# Pyr0-Piezo_Direct_Extruder_Board2_3_1.net
KiCad netlist of a schematic drawn in EAGLE
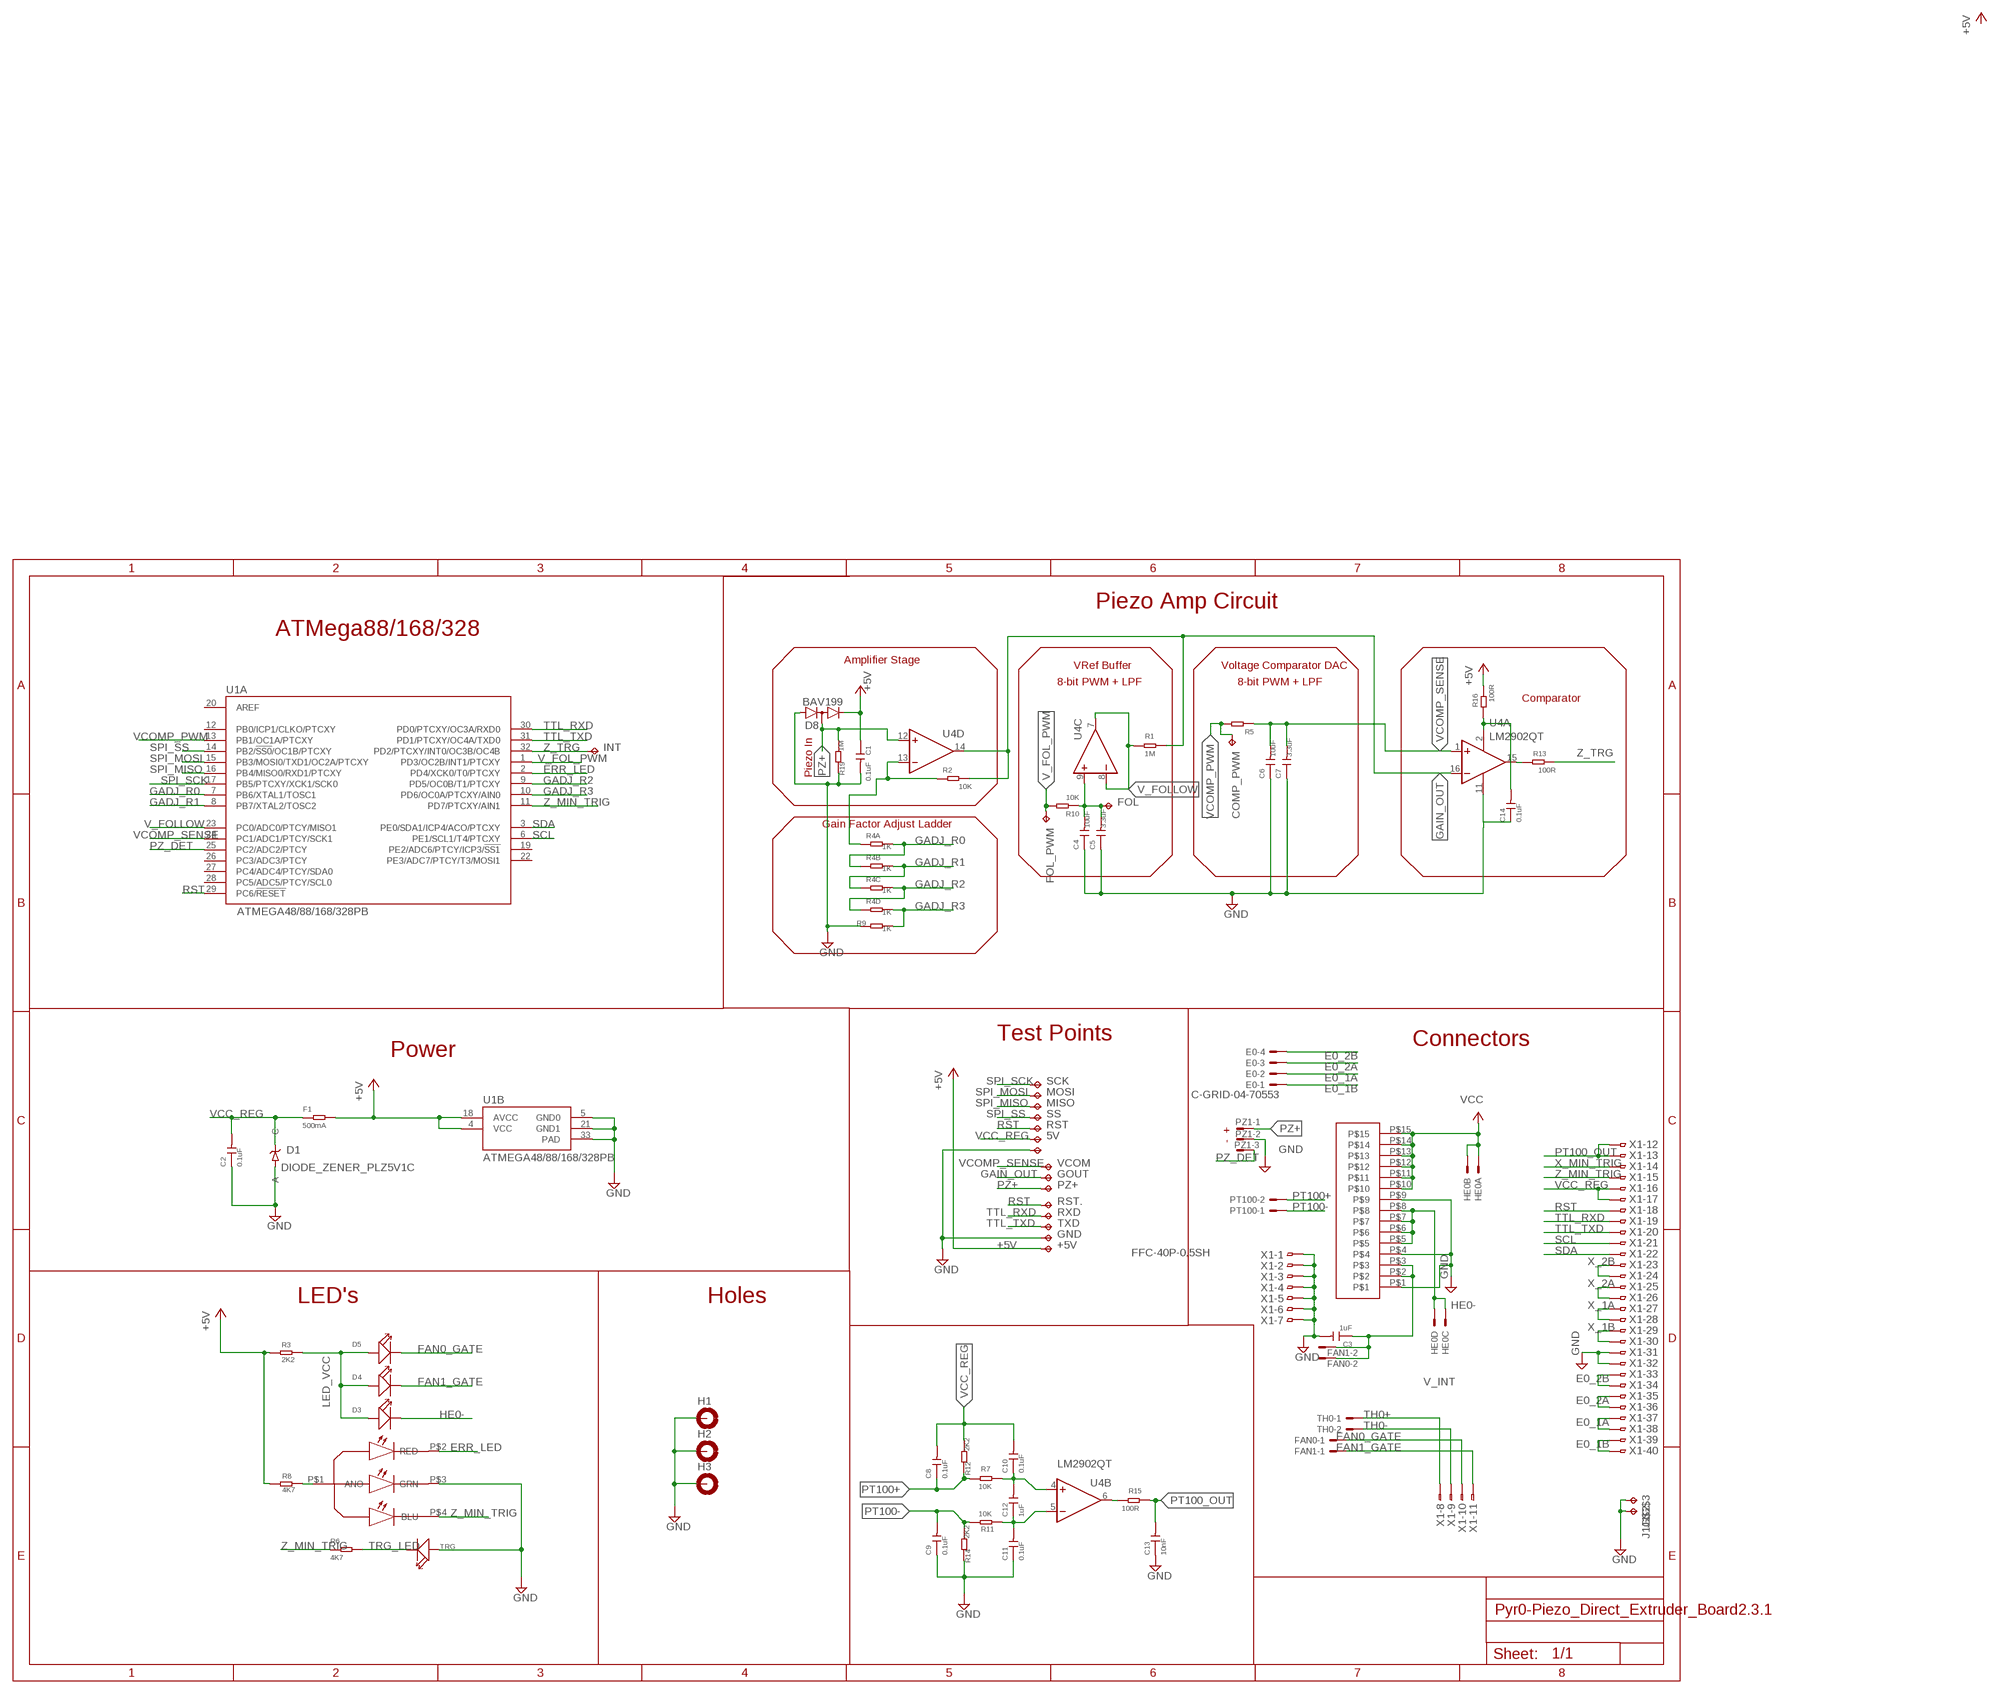
[diagram p0: schematic, sheet 1]

(export (version "E")
  (design (tool "Eeschema 10.0.6"))
  (components
    (comp (ref "+5V")
      (value "TPTP13SQ")
      (footprint "eagle-import:TP13SQ")
      (libsource (lib "eagle-import") (part "testpad_385_TPTP13SQ"))
    )
    (comp (ref "5V")
      (value "TPTP13SQ")
      (footprint "eagle-import:TP13SQ")
      (libsource (lib "eagle-import") (part "TPTP13SQ"))
    )
    (comp (ref "C1")
      (value "0.1uF")
      (footprint "eagle-import:CAPC2012X130")
      (libsource (lib "eagle-import") (part "SEEED-CAPACITOR_CERAMIC-10UF-25V-10%-X5R(0805)CAP_0805-3D"))
    )
    (comp (ref "C2")
      (value "0.1uF")
      (footprint "eagle-import:CAPC1005X50")
      (libsource (lib "eagle-import") (part "CERAMIC-1NF-50V-10%-X7R(0402)CAP_0402"))
    )
    (comp (ref "C3")
      (value "1uF")
      (footprint "eagle-import:CAPC1609X80")
      (libsource (lib "eagle-import") (part "SEEED-CAPACITOR_CERAMIC-10UF-25V-10%-X5R(0805)CAP_0603_GEN"))
    )
    (comp (ref "C4")
      (value "10uF")
      (footprint "eagle-import:CAPC1005X50")
      (libsource (lib "eagle-import") (part "CERAMIC-1NF-50V-10%-X7R(0402)CAP_0402"))
    )
    (comp (ref "C5")
      (value "3.3uF")
      (footprint "eagle-import:CAPC1609X80")
      (libsource (lib "eagle-import") (part "SEEED-CAPACITOR_CERAMIC-10UF-25V-10%-X5R(0805)CAP_0603_GEN"))
    )
    (comp (ref "C6")
      (value "10uF")
      (footprint "eagle-import:CAPC1005X50")
      (libsource (lib "eagle-import") (part "CERAMIC-1NF-50V-10%-X7R(0402)CAP_0402"))
    )
    (comp (ref "C7")
      (value "3.3uF")
      (footprint "eagle-import:CAPC1609X80")
      (libsource (lib "eagle-import") (part "SEEED-CAPACITOR_CERAMIC-10UF-25V-10%-X5R(0805)CAP_0603_GEN"))
    )
    (comp (ref "C8")
      (value "0.1uF")
      (footprint "eagle-import:CAPC1005X50")
      (libsource (lib "eagle-import") (part "CERAMIC-1NF-50V-10%-X7R(0402)CAP_0402"))
    )
    (comp (ref "C9")
      (value "0.1uF")
      (footprint "eagle-import:CAPC1005X50")
      (libsource (lib "eagle-import") (part "CERAMIC-1NF-50V-10%-X7R(0402)CAP_0402"))
    )
    (comp (ref "C10")
      (value "0.1uF")
      (footprint "eagle-import:CAPC1005X50")
      (libsource (lib "eagle-import") (part "CERAMIC-1NF-50V-10%-X7R(0402)CAP_0402"))
    )
    (comp (ref "C11")
      (value "0.1uF")
      (footprint "eagle-import:CAPC1005X50")
      (libsource (lib "eagle-import") (part "CERAMIC-1NF-50V-10%-X7R(0402)CAP_0402"))
    )
    (comp (ref "C12")
      (value "1uF")
      (footprint "eagle-import:CAPC1005X50")
      (libsource (lib "eagle-import") (part "CERAMIC-1NF-50V-10%-X7R(0402)CAP_0402"))
    )
    (comp (ref "C13")
      (value "10nF")
      (footprint "eagle-import:CAPC1005X50")
      (libsource (lib "eagle-import") (part "CERAMIC-1NF-50V-10%-X7R(0402)CAP_0402"))
    )
    (comp (ref "C14")
      (value "0.1uF")
      (footprint "eagle-import:CAPC1005X50")
      (libsource (lib "eagle-import") (part "CERAMIC-1NF-50V-10%-X7R(0402)CAP_0402"))
    )
    (comp (ref "COMP_PWM")
      (value "TPTP09R")
      (footprint "eagle-import:TP09R")
      (libsource (lib "eagle-import") (part "TPTP09R"))
    )
    (comp (ref "D1")
      (value "DIODE_ZENER_PLZ5V1C")
      (footprint "eagle-import:DO-219AC")
      (libsource (lib "eagle-import") (part "DIODE_ZENER_PLZ5V1C"))
    )
    (comp (ref "D2")
      (value "LED-RGB-COM_ANO4PLCC")
      (footprint "eagle-import:4PLCC")
      (libsource (lib "eagle-import") (part "LED-RGB-COM_ANO4PLCC"))
    )
    (comp (ref "D3")
      (value "SEEED-LED_SMD-LED-CLEAR-BLUE(0603)LED_0603")
      (footprint "eagle-import:SEEED-LED_LED-0603")
      (libsource (lib "eagle-import") (part "SEEED-LED_SMD-LED-CLEAR-BLUE(0603)LED_0603"))
    )
    (comp (ref "D4")
      (value "SEEED-LED_SMD-LED-CLEAR-BLUE(0603)LED_0603")
      (footprint "eagle-import:SEEED-LED_LED-0603")
      (libsource (lib "eagle-import") (part "SEEED-LED_SMD-LED-CLEAR-BLUE(0603)LED_0603"))
    )
    (comp (ref "D5")
      (value "SEEED-LED_SMD-LED-CLEAR-BLUE(0603)LED_0603")
      (footprint "eagle-import:SEEED-LED_LED-0603")
      (libsource (lib "eagle-import") (part "SEEED-LED_SMD-LED-CLEAR-BLUE(0603)LED_0603"))
    )
    (comp (ref "D8")
      (value "BAV199")
      (footprint "eagle-import:SOT23")
      (libsource (lib "eagle-import") (part "BAV199"))
    )
    (comp (ref "E0")
      (value "C-GRID-04-70553")
      (footprint "eagle-import:70553-04")
      (fields (field (name "MF") "MOLEX"))
      (libsource (lib "eagle-import") (part "C-GRID-04-70553"))
    )
    (comp (ref "F1")
      (value "500mA")
      (footprint "eagle-import:SEEED-RESISTOR_R0603")
      (libsource (lib "eagle-import") (part "SEEED-RESISTOR_SMD-RES-1.5K-1%-1/10W(0603)DETAILED_MODEL"))
    )
    (comp (ref "FAN0")
      (value "CON-MOLEX-2P-1.27MM048")
      (footprint "eagle-import:53048-02")
      (fields (field (name "MF") "MOLEX") (field (name "MPN") "53048-0210"))
      (libsource (lib "eagle-import") (part "CON-MOLEX-2P-1.27MM048"))
    )
    (comp (ref "FAN1")
      (value "CON-MOLEX-2P-1.27MM048")
      (footprint "eagle-import:53048-02")
      (fields (field (name "MF") "MOLEX") (field (name "MPN") "53048-0210"))
      (libsource (lib "eagle-import") (part "CON-MOLEX-2P-1.27MM048"))
    )
    (comp (ref "FOL")
      (value "TPTP13SQ")
      (footprint "eagle-import:TP13SQ")
      (libsource (lib "eagle-import") (part "TPTP13SQ"))
    )
    (comp (ref "FOL_PWM")
      (value "TPTP09R")
      (footprint "eagle-import:TP09R")
      (libsource (lib "eagle-import") (part "TPTP09R"))
    )
    (comp (ref "GND")
      (value "TPTP13SQ")
      (footprint "eagle-import:TP13SQ")
      (libsource (lib "eagle-import") (part "testpad_385_TPTP13SQ"))
    )
    (comp (ref "GOUT")
      (value "TPTP13SQ")
      (footprint "eagle-import:TP13SQ")
      (libsource (lib "eagle-import") (part "TPTP13SQ"))
    )
    (comp (ref "H1")
      (value "HOLES_MOUNT-PAD-ROUND3.2")
      (footprint "eagle-import:HOLES_3,2-PAD")
      (libsource (lib "eagle-import") (part "HOLES_MOUNT-PAD-ROUND3.2"))
    )
    (comp (ref "H2")
      (value "HOLES_MOUNT-PAD-ROUND3.2")
      (footprint "eagle-import:HOLES_3,2-PAD")
      (libsource (lib "eagle-import") (part "HOLES_MOUNT-PAD-ROUND3.2"))
    )
    (comp (ref "H3")
      (value "HOLES_MOUNT-PAD-ROUND3.2")
      (footprint "eagle-import:HOLES_3,2-PAD")
      (libsource (lib "eagle-import") (part "HOLES_MOUNT-PAD-ROUND3.2"))
    )
    (comp (ref "HE0")
      (value "JST-2.54-2X2JST-DUPONT-2.54-2X2")
      (footprint "eagle-import:HDRRAR4W64P254_2X2_556X736X556B")
      (libsource (lib "eagle-import") (part "JST-2.54-2X2JST-DUPONT-2.54-2X2"))
    )
    (comp (ref "INT")
      (value "TPTP13R")
      (footprint "eagle-import:TP13R")
      (libsource (lib "eagle-import") (part "TPTP13R"))
    )
    (comp (ref "J1")
      (value "FFC-15P-1MM")
      (footprint "eagle-import:FFC-15P-1MM")
      (libsource (lib "eagle-import") (part "FFC-15P-1MM"))
    )
    (comp (ref "MISO")
      (value "TPTP13SQ")
      (footprint "eagle-import:TP13SQ")
      (libsource (lib "eagle-import") (part "TPTP13SQ"))
    )
    (comp (ref "MOSI")
      (value "TPTP13SQ")
      (footprint "eagle-import:TP13SQ")
      (libsource (lib "eagle-import") (part "TPTP13SQ"))
    )
    (comp (ref "PT100")
      (value "CON-MOLEX-2P-1.27MM048")
      (footprint "eagle-import:53048-02")
      (fields (field (name "MF") "MOLEX") (field (name "MPN") "53048-0210"))
      (libsource (lib "eagle-import") (part "CON-MOLEX-2P-1.27MM048"))
    )
    (comp (ref "PZ+")
      (value "TPTP13SQ")
      (footprint "eagle-import:TP13SQ")
      (libsource (lib "eagle-import") (part "TPTP13SQ"))
    )
    (comp (ref "PZ1")
      (value "CON-MOLEX-3P-1.25MM048")
      (footprint "eagle-import:53048-03")
      (fields (field (name "MF") "WALDOM/MOLEX") (field (name "MPN") "53048-0310"))
      (libsource (lib "eagle-import") (part "CON-MOLEX-3P-1.25MM048"))
    )
    (comp (ref "R1")
      (value "1M")
      (footprint "eagle-import:R0402")
      (fields (field (name "MPN") "RC0402JR-070RL"))
      (libsource (lib "eagle-import") (part "SMD-RES-0R-5%-1/16W(0402)"))
    )
    (comp (ref "R2")
      (value "10K")
      (footprint "eagle-import:R0402")
      (fields (field (name "MPN") "RC0402JR-070RL"))
      (libsource (lib "eagle-import") (part "SMD-RES-0R-5%-1/16W(0402)"))
    )
    (comp (ref "R3")
      (value "2K2")
      (footprint "eagle-import:R0402")
      (fields (field (name "MPN") "RC0402JR-070RL"))
      (libsource (lib "eagle-import") (part "SMD-RES-0R-5%-1/16W(0402)"))
    )
    (comp (ref "R4")
      (value "1K")
      (footprint "eagle-import:EXBN8V")
      (libsource (lib "eagle-import") (part "RESISTOR_NETWORK_X40804"))
    )
    (comp (ref "R5")
      (value "0R")
      (footprint "eagle-import:R0402")
      (fields (field (name "MPN") "RC0402JR-070RL"))
      (libsource (lib "eagle-import") (part "SMD-RES-0R-5%-1/16W(0402)"))
    )
    (comp (ref "R6")
      (value "4K7")
      (footprint "eagle-import:R0402")
      (fields (field (name "MPN") "RC0402JR-070RL"))
      (libsource (lib "eagle-import") (part "SMD-RES-0R-5%-1/16W(0402)"))
    )
    (comp (ref "R7")
      (value "10K")
      (footprint "eagle-import:R0402")
      (fields (field (name "MPN") "RC0402JR-070RL"))
      (libsource (lib "eagle-import") (part "SMD-RES-0R-5%-1/16W(0402)"))
    )
    (comp (ref "R8")
      (value "4K7")
      (footprint "eagle-import:R0402")
      (fields (field (name "MPN") "RC0402JR-070RL"))
      (libsource (lib "eagle-import") (part "SMD-RES-0R-5%-1/16W(0402)"))
    )
    (comp (ref "R9")
      (value "1K")
      (footprint "eagle-import:R0402")
      (fields (field (name "MPN") "RC0402JR-070RL"))
      (libsource (lib "eagle-import") (part "SMD-RES-0R-5%-1/16W(0402)"))
    )
    (comp (ref "R10")
      (value "10K")
      (footprint "eagle-import:R0402")
      (fields (field (name "MPN") "RC0402JR-070RL"))
      (libsource (lib "eagle-import") (part "SMD-RES-0R-5%-1/16W(0402)"))
    )
    (comp (ref "R11")
      (value "10K")
      (footprint "eagle-import:R0402")
      (fields (field (name "MPN") "RC0402JR-070RL"))
      (libsource (lib "eagle-import") (part "SMD-RES-0R-5%-1/16W(0402)"))
    )
    (comp (ref "R12")
      (value "2K2")
      (footprint "eagle-import:R0402")
      (fields (field (name "MPN") "RC0402JR-070RL"))
      (libsource (lib "eagle-import") (part "SMD-RES-0R-5%-1/16W(0402)"))
    )
    (comp (ref "R13")
      (value "100R")
      (footprint "eagle-import:R0402")
      (fields (field (name "MPN") "RC0402JR-070RL"))
      (libsource (lib "eagle-import") (part "SMD-RES-0R-5%-1/16W(0402)"))
    )
    (comp (ref "R14")
      (value "2K2")
      (footprint "eagle-import:R0402")
      (fields (field (name "MPN") "RC0402JR-070RL"))
      (libsource (lib "eagle-import") (part "SMD-RES-0R-5%-1/16W(0402)"))
    )
    (comp (ref "R15")
      (value "100R")
      (footprint "eagle-import:R0402")
      (fields (field (name "MPN") "RC0402JR-070RL"))
      (libsource (lib "eagle-import") (part "SMD-RES-0R-5%-1/16W(0402)"))
    )
    (comp (ref "R16")
      (value "100R")
      (footprint "eagle-import:R0402")
      (fields (field (name "MPN") "RC0402JR-070RL"))
      (libsource (lib "eagle-import") (part "SMD-RES-0R-5%-1/16W(0402)"))
    )
    (comp (ref "R19")
      (value "1M")
      (footprint "eagle-import:R0402")
      (fields (field (name "MPN") "RC0402JR-070RL"))
      (libsource (lib "eagle-import") (part "SMD-RES-0R-5%-1/16W(0402)"))
    )
    (comp (ref "RST")
      (value "TPTP13SQ")
      (footprint "eagle-import:TP13SQ")
      (libsource (lib "eagle-import") (part "TPTP13SQ"))
    )
    (comp (ref "RST.")
      (value "TPTP13SQ")
      (footprint "eagle-import:TP13SQ")
      (libsource (lib "eagle-import") (part "testpad_385_TPTP13SQ"))
    )
    (comp (ref "RXD")
      (value "TPTP13SQ")
      (footprint "eagle-import:TP13SQ")
      (libsource (lib "eagle-import") (part "testpad_385_TPTP13SQ"))
    )
    (comp (ref "SCK")
      (value "TPTP13SQ")
      (footprint "eagle-import:TP13SQ")
      (libsource (lib "eagle-import") (part "TPTP13SQ"))
    )
    (comp (ref "SS")
      (value "TPTP06R")
      (footprint "eagle-import:TP06R")
      (libsource (lib "eagle-import") (part "testpad_385_TPTP06R"))
    )
    (comp (ref "TH0")
      (value "CON-MOLEX-2P-1.27MM048")
      (footprint "eagle-import:53048-02")
      (fields (field (name "MF") "MOLEX") (field (name "MPN") "53048-0210"))
      (libsource (lib "eagle-import") (part "CON-MOLEX-2P-1.27MM048"))
    )
    (comp (ref "TRG")
      (value "SEEED-LED_SMD-LED-CLEAR-BLUE(0603)LED_0603")
      (footprint "eagle-import:SEEED-LED_LED-0603")
      (libsource (lib "eagle-import") (part "SEEED-LED_SMD-LED-CLEAR-BLUE(0603)LED_0603"))
    )
    (comp (ref "TXD")
      (value "TPTP13SQ")
      (footprint "eagle-import:TP13SQ")
      (libsource (lib "eagle-import") (part "testpad_385_TPTP13SQ"))
    )
    (comp (ref "U1")
      (value "ATMEGA48/88/168/328PB")
      (footprint "eagle-import:QFN50P500X500X90-33N")
      (fields (field (name "MF") "Microchip") (field (name "MP") "ATMEGA328PB-MU"))
      (libsource (lib "eagle-import") (part "ATMEGA48/88/168/328PB"))
    )
    (comp (ref "U4")
      (value "LM2902QT")
      (footprint "eagle-import:QFN16")
      (libsource (lib "eagle-import") (part "LM2902QT"))
    )
    (comp (ref "VCOM")
      (value "TPTP13SQ")
      (footprint "eagle-import:TP13SQ")
      (libsource (lib "eagle-import") (part "TPTP13SQ"))
    )
    (comp (ref "X1")
      (value "FFC-40P-0.5SH")
      (footprint "eagle-import:FH12-40S-0.5SH")
      (fields (field (name "MPN") "FH12-40S-0.5SH(55)"))
      (libsource (lib "eagle-import") (part "FFC-40P-0.5SH"))
    )
    (comp (ref "⏚")
      (value "TPTP13SQ")
      (footprint "eagle-import:TP13SQ")
      (libsource (lib "eagle-import") (part "testpad_385_TPTP13SQ"))
    )
  )
  (nets
    (net (code "1") (name "+5V") (class "Default")
      (node (ref "+5V") (pin "TP") (pinfunction "TP_TP") (pintype "input"))
      (node (ref "C1") (pin "1") (pinfunction "1_1") (pintype "passive"))
      (node (ref "D8") (pin "2") (pinfunction "C_2") (pintype "passive"))
      (node (ref "F1") (pin "2") (pinfunction "2_2") (pintype "passive"))
      (node (ref "R16") (pin "2") (pinfunction "2_2") (pintype "passive"))
      (node (ref "R3") (pin "1") (pinfunction "1_1") (pintype "passive"))
      (node (ref "R8") (pin "1") (pinfunction "1_1") (pintype "passive"))
      (node (ref "U1") (pin "18") (pinfunction "AVCC_18") (pintype "power_in"))
      (node (ref "U1") (pin "4") (pinfunction "VCC_4") (pintype "power_in"))
    )
    (net (code "2") (name "/E0_1A") (class "Default")
      (node (ref "E0") (pin "2") (pinfunction "S_2") (pintype "passive"))
      (node (ref "X1") (pin "37") (pinfunction "1_37") (pintype "passive"))
      (node (ref "X1") (pin "38") (pinfunction "1_38") (pintype "passive"))
    )
    (net (code "3") (name "/E0_1B") (class "Default")
      (node (ref "E0") (pin "1") (pinfunction "S_1") (pintype "passive"))
      (node (ref "X1") (pin "39") (pinfunction "1_39") (pintype "passive"))
      (node (ref "X1") (pin "40") (pinfunction "1_40") (pintype "passive"))
    )
    (net (code "4") (name "/E0_2A") (class "Default")
      (node (ref "E0") (pin "3") (pinfunction "S_3") (pintype "passive"))
      (node (ref "X1") (pin "35") (pinfunction "1_35") (pintype "passive"))
      (node (ref "X1") (pin "36") (pinfunction "1_36") (pintype "passive"))
    )
    (net (code "5") (name "/E0_2B") (class "Default")
      (node (ref "E0") (pin "4") (pinfunction "S_4") (pintype "passive"))
      (node (ref "X1") (pin "33") (pinfunction "1_33") (pintype "passive"))
      (node (ref "X1") (pin "34") (pinfunction "1_34") (pintype "passive"))
    )
    (net (code "6") (name "/ERR_LED") (class "Default")
      (node (ref "D2") (pin "P$2") (pinfunction "RED_P$2") (pintype "bidirectional"))
      (node (ref "U1") (pin "2") (pinfunction "PD4/XCK0/T0/PTCXY_2") (pintype "bidirectional"))
    )
    (net (code "7") (name "/FAN0_GATE") (class "Default")
      (node (ref "D5") (pin "-") (pinfunction "-_-") (pintype "passive"))
      (node (ref "FAN0") (pin "1") (pinfunction "S_1") (pintype "passive"))
      (node (ref "X1") (pin "10") (pinfunction "1_10") (pintype "passive"))
    )
    (net (code "8") (name "/FAN1_GATE") (class "Default")
      (node (ref "D4") (pin "-") (pinfunction "-_-") (pintype "passive"))
      (node (ref "FAN1") (pin "1") (pinfunction "S_1") (pintype "passive"))
      (node (ref "X1") (pin "11") (pinfunction "1_11") (pintype "passive"))
    )
    (net (code "9") (name "/GADJ_R0") (class "Default")
      (node (ref "R4") (pin "2") (pinfunction "1_2") (pintype "passive"))
      (node (ref "R4") (pin "8") (pinfunction "2_8") (pintype "passive"))
      (node (ref "U1") (pin "7") (pinfunction "PB6/XTAL1/TOSC1_7") (pintype "bidirectional"))
    )
    (net (code "10") (name "/GADJ_R1") (class "Default")
      (node (ref "R4") (pin "3") (pinfunction "1_3") (pintype "passive"))
      (node (ref "R4") (pin "7") (pinfunction "2_7") (pintype "passive"))
      (node (ref "U1") (pin "8") (pinfunction "PB7/XTAL2/TOSC2_8") (pintype "bidirectional"))
    )
    (net (code "11") (name "/GADJ_R2") (class "Default")
      (node (ref "R4") (pin "4") (pinfunction "1_4") (pintype "passive"))
      (node (ref "R4") (pin "6") (pinfunction "2_6") (pintype "passive"))
      (node (ref "U1") (pin "9") (pinfunction "PD5/OC0B/T1/PTCXY_9") (pintype "bidirectional"))
    )
    (net (code "12") (name "/GADJ_R3") (class "Default")
      (node (ref "R4") (pin "5") (pinfunction "2_5") (pintype "passive"))
      (node (ref "R9") (pin "2") (pinfunction "2_2") (pintype "passive"))
      (node (ref "U1") (pin "10") (pinfunction "PD6/OC0A/PTCXY/AIN0_10") (pintype "bidirectional"))
    )
    (net (code "13") (name "/HE0-") (class "Default")
      (node (ref "D3") (pin "-") (pinfunction "-_-") (pintype "passive"))
      (node (ref "HE0") (pin "3") (pinfunction "S_3") (pintype "passive"))
      (node (ref "HE0") (pin "4") (pinfunction "S_4") (pintype "passive"))
      (node (ref "J1") (pin "P$5") (pinfunction "P$5_P$5") (pintype "bidirectional"))
      (node (ref "J1") (pin "P$6") (pinfunction "P$6_P$6") (pintype "bidirectional"))
      (node (ref "J1") (pin "P$7") (pinfunction "P$7_P$7") (pintype "bidirectional"))
      (node (ref "J1") (pin "P$8") (pinfunction "P$8_P$8") (pintype "bidirectional"))
    )
    (net (code "14") (name "/LED_VCC") (class "Default")
      (node (ref "D3") (pin "+") (pinfunction "+_+") (pintype "passive"))
      (node (ref "D4") (pin "+") (pinfunction "+_+") (pintype "passive"))
      (node (ref "D5") (pin "+") (pinfunction "+_+") (pintype "passive"))
      (node (ref "R3") (pin "2") (pinfunction "2_2") (pintype "passive"))
    )
    (net (code "15") (name "/PZ_DET") (class "Default")
      (node (ref "PZ1") (pin "3") (pinfunction "S_3") (pintype "passive"))
      (node (ref "U1") (pin "25") (pinfunction "PC2/ADC2/PTCY_25") (pintype "bidirectional"))
    )
    (net (code "16") (name "/RST") (class "Default")
      (node (ref "RST") (pin "TP") (pinfunction "TP_TP") (pintype "input"))
      (node (ref "RST.") (pin "TP") (pinfunction "TP_TP") (pintype "input"))
      (node (ref "U1") (pin "29") (pinfunction "PC6/~{RESET}_29") (pintype "bidirectional"))
      (node (ref "X1") (pin "18") (pinfunction "1_18") (pintype "passive"))
    )
    (net (code "17") (name "/SCL") (class "Default")
      (node (ref "U1") (pin "6") (pinfunction "PE1/SCL1/T4/PTCXY_6") (pintype "bidirectional"))
      (node (ref "X1") (pin "21") (pinfunction "1_21") (pintype "passive"))
    )
    (net (code "18") (name "/SDA") (class "Default")
      (node (ref "U1") (pin "3") (pinfunction "PE0/SDA1/ICP4/ACO/PTCXY_3") (pintype "bidirectional"))
      (node (ref "X1") (pin "22") (pinfunction "1_22") (pintype "passive"))
    )
    (net (code "19") (name "/SPI_MISO") (class "Default")
      (node (ref "MISO") (pin "TP") (pinfunction "TP_TP") (pintype "input"))
      (node (ref "U1") (pin "16") (pinfunction "PB4/MISO0/RXD1/PTCXY_16") (pintype "bidirectional"))
    )
    (net (code "20") (name "/SPI_MOSI") (class "Default")
      (node (ref "MOSI") (pin "TP") (pinfunction "TP_TP") (pintype "input"))
      (node (ref "U1") (pin "15") (pinfunction "PB3/MOSI0/TXD1/OC2A/PTCXY_15") (pintype "bidirectional"))
    )
    (net (code "21") (name "/SPI_SCK") (class "Default")
      (node (ref "SCK") (pin "TP") (pinfunction "TP_TP") (pintype "input"))
      (node (ref "U1") (pin "17") (pinfunction "PB5/PTCXY/XCK1/SCK0_17") (pintype "bidirectional"))
    )
    (net (code "22") (name "/SPI_SS") (class "Default")
      (node (ref "SS") (pin "TP") (pinfunction "TP_TP") (pintype "input"))
      (node (ref "U1") (pin "14") (pinfunction "PB2/~{SS0}/OC1B/PTCXY_14") (pintype "bidirectional"))
    )
    (net (code "23") (name "/TH0+") (class "Default")
      (node (ref "TH0") (pin "1") (pinfunction "S_1") (pintype "passive"))
      (node (ref "X1") (pin "8") (pinfunction "1_8") (pintype "passive"))
    )
    (net (code "24") (name "/TH0-") (class "Default")
      (node (ref "TH0") (pin "2") (pinfunction "S_2") (pintype "passive"))
      (node (ref "X1") (pin "9") (pinfunction "1_9") (pintype "passive"))
    )
    (net (code "25") (name "/TRG_LED") (class "Default")
      (node (ref "R6") (pin "2") (pinfunction "2_2") (pintype "passive"))
      (node (ref "TRG") (pin "-") (pinfunction "-_-") (pintype "passive"))
    )
    (net (code "26") (name "/TTL_RXD") (class "Default")
      (node (ref "RXD") (pin "TP") (pinfunction "TP_TP") (pintype "input"))
      (node (ref "U1") (pin "30") (pinfunction "PD0/PTCXY/OC3A/RXD0_30") (pintype "bidirectional"))
      (node (ref "X1") (pin "19") (pinfunction "1_19") (pintype "passive"))
    )
    (net (code "27") (name "/TTL_TXD") (class "Default")
      (node (ref "TXD") (pin "TP") (pinfunction "TP_TP") (pintype "input"))
      (node (ref "U1") (pin "31") (pinfunction "PD1/PTCXY/OC4A/TXD0_31") (pintype "bidirectional"))
      (node (ref "X1") (pin "20") (pinfunction "1_20") (pintype "passive"))
    )
    (net (code "28") (name "/V_INT") (class "Default")
      (node (ref "C3") (pin "1") (pinfunction "1_1") (pintype "passive"))
      (node (ref "FAN0") (pin "2") (pinfunction "S_2") (pintype "passive"))
      (node (ref "FAN1") (pin "2") (pinfunction "S_2") (pintype "passive"))
      (node (ref "J1") (pin "P$2") (pinfunction "P$2_P$2") (pintype "bidirectional"))
      (node (ref "J1") (pin "P$3") (pinfunction "P$3_P$3") (pintype "bidirectional"))
    )
    (net (code "29") (name "/X_1A") (class "Default")
      (node (ref "X1") (pin "27") (pinfunction "1_27") (pintype "passive"))
      (node (ref "X1") (pin "28") (pinfunction "1_28") (pintype "passive"))
    )
    (net (code "30") (name "/X_1B") (class "Default")
      (node (ref "X1") (pin "29") (pinfunction "1_29") (pintype "passive"))
      (node (ref "X1") (pin "30") (pinfunction "1_30") (pintype "passive"))
    )
    (net (code "31") (name "/X_2A") (class "Default")
      (node (ref "X1") (pin "25") (pinfunction "1_25") (pintype "passive"))
      (node (ref "X1") (pin "26") (pinfunction "1_26") (pintype "passive"))
    )
    (net (code "32") (name "/X_2B") (class "Default")
      (node (ref "X1") (pin "23") (pinfunction "1_23") (pintype "passive"))
      (node (ref "X1") (pin "24") (pinfunction "1_24") (pintype "passive"))
    )
    (net (code "33") (name "/X_MIN_TRIG") (class "Default")
      (node (ref "X1") (pin "14") (pinfunction "1_14") (pintype "passive"))
    )
    (net (code "34") (name "/Z_MIN_TRIG") (class "Default")
      (node (ref "D2") (pin "P$4") (pinfunction "BLU_P$4") (pintype "bidirectional"))
      (node (ref "R6") (pin "1") (pinfunction "1_1") (pintype "passive"))
      (node (ref "U1") (pin "11") (pinfunction "PD7/PTCXY/AIN1_11") (pintype "bidirectional"))
      (node (ref "X1") (pin "15") (pinfunction "1_15") (pintype "passive"))
    )
    (net (code "35") (name "/Z_TRG") (class "Default")
      (node (ref "INT") (pin "TP") (pinfunction "TP_TP") (pintype "input"))
      (node (ref "R13") (pin "2") (pinfunction "2_2") (pintype "passive"))
      (node (ref "U1") (pin "32") (pinfunction "PD2/PTCXY/INT0/OC3B/OC4B_32") (pintype "bidirectional"))
    )
    (net (code "36") (name "GAIN_OUT") (class "Default")
      (node (ref "GOUT") (pin "TP") (pinfunction "TP_TP") (pintype "input"))
      (node (ref "R1") (pin "2") (pinfunction "2_2") (pintype "passive"))
      (node (ref "R2") (pin "2") (pinfunction "2_2") (pintype "passive"))
      (node (ref "U4") (pin "14") (pinfunction "OUT_14") (pintype "output"))
      (node (ref "U4") (pin "16") (pinfunction "-IN_16") (pintype "input"))
    )
    (net (code "37") (name "GND") (class "Default")
      (node (ref "C1") (pin "2") (pinfunction "2_2") (pintype "passive"))
      (node (ref "C11") (pin "1") (pinfunction "1_1") (pintype "passive"))
      (node (ref "C13") (pin "1") (pinfunction "1_1") (pintype "passive"))
      (node (ref "C14") (pin "1") (pinfunction "1_1") (pintype "passive"))
      (node (ref "C2") (pin "1") (pinfunction "1_1") (pintype "passive"))
      (node (ref "C3") (pin "2") (pinfunction "2_2") (pintype "passive"))
      (node (ref "C4") (pin "1") (pinfunction "1_1") (pintype "passive"))
      (node (ref "C5") (pin "1") (pinfunction "1_1") (pintype "passive"))
      (node (ref "C6") (pin "1") (pinfunction "1_1") (pintype "passive"))
      (node (ref "C7") (pin "1") (pinfunction "1_1") (pintype "passive"))
      (node (ref "C9") (pin "1") (pinfunction "1_1") (pintype "passive"))
      (node (ref "D1") (pin "P$1") (pinfunction "A_P$1") (pintype "passive"))
      (node (ref "D2") (pin "P$3") (pinfunction "GRN_P$3") (pintype "bidirectional"))
      (node (ref "D8") (pin "1") (pinfunction "A_1") (pintype "passive"))
      (node (ref "GND") (pin "TP") (pinfunction "TP_TP") (pintype "input"))
      (node (ref "H1") (pin "B3,2") (pinfunction "MOUNT_B3,2") (pintype "passive"))
      (node (ref "H2") (pin "B3,2") (pinfunction "MOUNT_B3,2") (pintype "passive"))
      (node (ref "H3") (pin "B3,2") (pinfunction "MOUNT_B3,2") (pintype "passive"))
      (node (ref "J1") (pin "P$1") (pinfunction "P$1_P$1") (pintype "bidirectional"))
      (node (ref "J1") (pin "P$16") (pinfunction "TP_P$16") (pintype "input"))
      (node (ref "J1") (pin "P$17") (pinfunction "TP_P$17") (pintype "input"))
      (node (ref "J1") (pin "P$4") (pinfunction "P$4_P$4") (pintype "bidirectional"))
      (node (ref "J1") (pin "P$9") (pinfunction "P$9_P$9") (pintype "bidirectional"))
      (node (ref "PZ1") (pin "2") (pinfunction "S_2") (pintype "passive"))
      (node (ref "R14") (pin "1") (pinfunction "1_1") (pintype "passive"))
      (node (ref "R19") (pin "1") (pinfunction "1_1") (pintype "passive"))
      (node (ref "R9") (pin "1") (pinfunction "1_1") (pintype "passive"))
      (node (ref "TRG") (pin "+") (pinfunction "+_+") (pintype "passive"))
      (node (ref "U1") (pin "21") (pinfunction "GND1_21") (pintype "power_in"))
      (node (ref "U1") (pin "33") (pinfunction "PAD_33") (pintype "power_in"))
      (node (ref "U1") (pin "5") (pinfunction "GND0_5") (pintype "power_in"))
      (node (ref "U4") (pin "11") (pinfunction "V-_11") (pintype "power_in"))
      (node (ref "X1") (pin "1") (pinfunction "1_1") (pintype "passive"))
      (node (ref "X1") (pin "2") (pinfunction "1_2") (pintype "passive"))
      (node (ref "X1") (pin "3") (pinfunction "1_3") (pintype "passive"))
      (node (ref "X1") (pin "31") (pinfunction "1_31") (pintype "passive"))
      (node (ref "X1") (pin "32") (pinfunction "1_32") (pintype "passive"))
      (node (ref "X1") (pin "4") (pinfunction "1_4") (pintype "passive"))
      (node (ref "X1") (pin "5") (pinfunction "1_5") (pintype "passive"))
      (node (ref "X1") (pin "6") (pinfunction "1_6") (pintype "passive"))
      (node (ref "X1") (pin "7") (pinfunction "1_7") (pintype "passive"))
      (node (ref "⏚") (pin "TP") (pinfunction "TP_TP") (pintype "input"))
    )
    (net (code "38") (name "Net-(D2-ANO)") (class "Default")
      (node (ref "D2") (pin "P$1") (pinfunction "ANO_P$1") (pintype "bidirectional"))
      (node (ref "R8") (pin "2") (pinfunction "2_2") (pintype "passive"))
    )
    (net (code "39") (name "Net-(U4A-OUT)") (class "Default")
      (node (ref "R13") (pin "1") (pinfunction "1_1") (pintype "passive"))
      (node (ref "U4") (pin "15") (pinfunction "OUT_15") (pintype "output"))
    )
    (net (code "40") (name "Net-(U4B-+IN)") (class "Default")
      (node (ref "C10") (pin "1") (pinfunction "1_1") (pintype "passive"))
      (node (ref "C12") (pin "2") (pinfunction "2_2") (pintype "passive"))
      (node (ref "R7") (pin "1") (pinfunction "1_1") (pintype "passive"))
      (node (ref "U4") (pin "4") (pinfunction "+IN_4") (pintype "input"))
    )
    (net (code "41") (name "Net-(U4B--IN)") (class "Default")
      (node (ref "C11") (pin "2") (pinfunction "2_2") (pintype "passive"))
      (node (ref "C12") (pin "1") (pinfunction "1_1") (pintype "passive"))
      (node (ref "R11") (pin "1") (pinfunction "1_1") (pintype "passive"))
      (node (ref "U4") (pin "5") (pinfunction "-IN_5") (pintype "input"))
    )
    (net (code "42") (name "Net-(U4B-OUT)") (class "Default")
      (node (ref "R15") (pin "2") (pinfunction "2_2") (pintype "passive"))
      (node (ref "U4") (pin "6") (pinfunction "OUT_6") (pintype "output"))
    )
    (net (code "43") (name "Net-(U4C-+IN)") (class "Default")
      (node (ref "C4") (pin "2") (pinfunction "2_2") (pintype "passive"))
      (node (ref "C5") (pin "2") (pinfunction "2_2") (pintype "passive"))
      (node (ref "FOL") (pin "TP") (pinfunction "TP_TP") (pintype "input"))
      (node (ref "R10") (pin "1") (pinfunction "1_1") (pintype "passive"))
      (node (ref "U4") (pin "9") (pinfunction "+IN_9") (pintype "input"))
    )
    (net (code "44") (name "Net-(U4D--IN)") (class "Default")
      (node (ref "R2") (pin "1") (pinfunction "1_1") (pintype "passive"))
      (node (ref "R4") (pin "1") (pinfunction "1_1") (pintype "passive"))
      (node (ref "U4") (pin "13") (pinfunction "-IN_13") (pintype "input"))
    )
    (net (code "45") (name "Net-(U4E-V+)") (class "Default")
      (node (ref "C14") (pin "2") (pinfunction "2_2") (pintype "passive"))
      (node (ref "R16") (pin "1") (pinfunction "1_1") (pintype "passive"))
      (node (ref "U4") (pin "2") (pinfunction "V+_2") (pintype "power_in"))
    )
    (net (code "46") (name "PT100+") (class "Default")
      (node (ref "C8") (pin "1") (pinfunction "1_1") (pintype "passive"))
      (node (ref "PT100") (pin "2") (pinfunction "S_2") (pintype "passive"))
      (node (ref "R12") (pin "1") (pinfunction "1_1") (pintype "passive"))
      (node (ref "R7") (pin "2") (pinfunction "2_2") (pintype "passive"))
    )
    (net (code "47") (name "PT100-") (class "Default")
      (node (ref "C9") (pin "2") (pinfunction "2_2") (pintype "passive"))
      (node (ref "PT100") (pin "1") (pinfunction "S_1") (pintype "passive"))
      (node (ref "R11") (pin "2") (pinfunction "2_2") (pintype "passive"))
      (node (ref "R14") (pin "2") (pinfunction "2_2") (pintype "passive"))
    )
    (net (code "48") (name "PT100_OUT") (class "Default")
      (node (ref "C13") (pin "2") (pinfunction "2_2") (pintype "passive"))
      (node (ref "R15") (pin "1") (pinfunction "1_1") (pintype "passive"))
      (node (ref "X1") (pin "12") (pinfunction "1_12") (pintype "passive"))
      (node (ref "X1") (pin "13") (pinfunction "1_13") (pintype "passive"))
    )
    (net (code "49") (name "PZ+") (class "Default")
      (node (ref "D8") (pin "3") (pinfunction "AC_3") (pintype "passive"))
      (node (ref "PZ+") (pin "TP") (pinfunction "TP_TP") (pintype "input"))
      (node (ref "PZ1") (pin "1") (pinfunction "S_1") (pintype "passive"))
      (node (ref "R19") (pin "2") (pinfunction "2_2") (pintype "passive"))
      (node (ref "U4") (pin "12") (pinfunction "+IN_12") (pintype "input"))
    )
    (net (code "50") (name "VCC") (class "Default")
      (node (ref "HE0") (pin "1") (pinfunction "S_1") (pintype "passive"))
      (node (ref "HE0") (pin "2") (pinfunction "S_2") (pintype "passive"))
      (node (ref "J1") (pin "P$10") (pinfunction "P$10_P$10") (pintype "bidirectional"))
      (node (ref "J1") (pin "P$11") (pinfunction "P$11_P$11") (pintype "bidirectional"))
      (node (ref "J1") (pin "P$12") (pinfunction "P$12_P$12") (pintype "bidirectional"))
      (node (ref "J1") (pin "P$13") (pinfunction "P$13_P$13") (pintype "bidirectional"))
      (node (ref "J1") (pin "P$14") (pinfunction "P$14_P$14") (pintype "bidirectional"))
      (node (ref "J1") (pin "P$15") (pinfunction "P$15_P$15") (pintype "bidirectional"))
    )
    (net (code "51") (name "VCC_REG") (class "Default")
      (node (ref "5V") (pin "TP") (pinfunction "TP_TP") (pintype "input"))
      (node (ref "C10") (pin "2") (pinfunction "2_2") (pintype "passive"))
      (node (ref "C2") (pin "2") (pinfunction "2_2") (pintype "passive"))
      (node (ref "C8") (pin "2") (pinfunction "2_2") (pintype "passive"))
      (node (ref "D1") (pin "P$2") (pinfunction "C_P$2") (pintype "passive"))
      (node (ref "F1") (pin "1") (pinfunction "1_1") (pintype "passive"))
      (node (ref "R12") (pin "2") (pinfunction "2_2") (pintype "passive"))
      (node (ref "X1") (pin "16") (pinfunction "1_16") (pintype "passive"))
      (node (ref "X1") (pin "17") (pinfunction "1_17") (pintype "passive"))
    )
    (net (code "52") (name "VCOMP_PWM") (class "Default")
      (node (ref "COMP_PWM") (pin "TP") (pinfunction "TP_TP") (pintype "input"))
      (node (ref "R5") (pin "2") (pinfunction "2_2") (pintype "passive"))
      (node (ref "U1") (pin "13") (pinfunction "PB1/OC1A/PTCXY_13") (pintype "bidirectional"))
    )
    (net (code "53") (name "VCOMP_SENSE") (class "Default")
      (node (ref "C6") (pin "2") (pinfunction "2_2") (pintype "passive"))
      (node (ref "C7") (pin "2") (pinfunction "2_2") (pintype "passive"))
      (node (ref "R5") (pin "1") (pinfunction "1_1") (pintype "passive"))
      (node (ref "U1") (pin "24") (pinfunction "PC1/ADC1/PTCY/SCK1_24") (pintype "bidirectional"))
      (node (ref "U4") (pin "1") (pinfunction "+IN_1") (pintype "input"))
      (node (ref "VCOM") (pin "TP") (pinfunction "TP_TP") (pintype "input"))
    )
    (net (code "54") (name "V_FOLLOW") (class "Default")
      (node (ref "R1") (pin "1") (pinfunction "1_1") (pintype "passive"))
      (node (ref "U1") (pin "23") (pinfunction "PC0/ADC0/PTCY/MISO1_23") (pintype "bidirectional"))
      (node (ref "U4") (pin "7") (pinfunction "OUT_7") (pintype "output"))
      (node (ref "U4") (pin "8") (pinfunction "-IN_8") (pintype "input"))
    )
    (net (code "55") (name "V_FOL_PWM") (class "Default")
      (node (ref "FOL_PWM") (pin "TP") (pinfunction "TP_TP") (pintype "input"))
      (node (ref "R10") (pin "2") (pinfunction "2_2") (pintype "passive"))
      (node (ref "U1") (pin "1") (pinfunction "PD3/OC2B/INT1/PTCXY_1") (pintype "bidirectional"))
    )
    (net (code "56") (name "unconnected-(U1A-AREF-Pad20)") (class "Default")
      (node (ref "U1") (pin "20") (pinfunction "AREF_20") (pintype "input"))
    )
    (net (code "57") (name "unconnected-(U1A-PB0{slash}ICP1{slash}CLKO{slash}PTCXY-Pad12)") (class "Default")
      (node (ref "U1") (pin "12") (pinfunction "PB0/ICP1/CLKO/PTCXY_12") (pintype "bidirectional"))
    )
    (net (code "58") (name "unconnected-(U1A-PC3{slash}ADC3{slash}PTCY-Pad26)") (class "Default")
      (node (ref "U1") (pin "26") (pinfunction "PC3/ADC3/PTCY_26") (pintype "bidirectional"))
    )
    (net (code "59") (name "unconnected-(U1A-PC4{slash}ADC4{slash}PTCY{slash}SDA0-Pad27)") (class "Default")
      (node (ref "U1") (pin "27") (pinfunction "PC4/ADC4/PTCY/SDA0_27") (pintype "bidirectional"))
    )
    (net (code "60") (name "unconnected-(U1A-PC5{slash}ADC5{slash}PTCY{slash}SCL0-Pad28)") (class "Default")
      (node (ref "U1") (pin "28") (pinfunction "PC5/ADC5/PTCY/SCL0_28") (pintype "bidirectional"))
    )
    (net (code "61") (name "unconnected-(U1A-PE2{slash}ADC6{slash}PTCY{slash}ICP3{slash}~{SS1}-Pad19)") (class "Default")
      (node (ref "U1") (pin "19") (pinfunction "PE2/ADC6/PTCY/ICP3/~{SS1}_19") (pintype "bidirectional"))
    )
    (net (code "62") (name "unconnected-(U1A-PE3{slash}ADC7{slash}PTCY{slash}T3{slash}MOSI1-Pad22)") (class "Default")
      (node (ref "U1") (pin "22") (pinfunction "PE3/ADC7/PTCY/T3/MOSI1_22") (pintype "bidirectional"))
    )
  )
)
